# MH-M38_Eagle_circuit.net
KiCad netlist of a schematic drawn in EAGLE
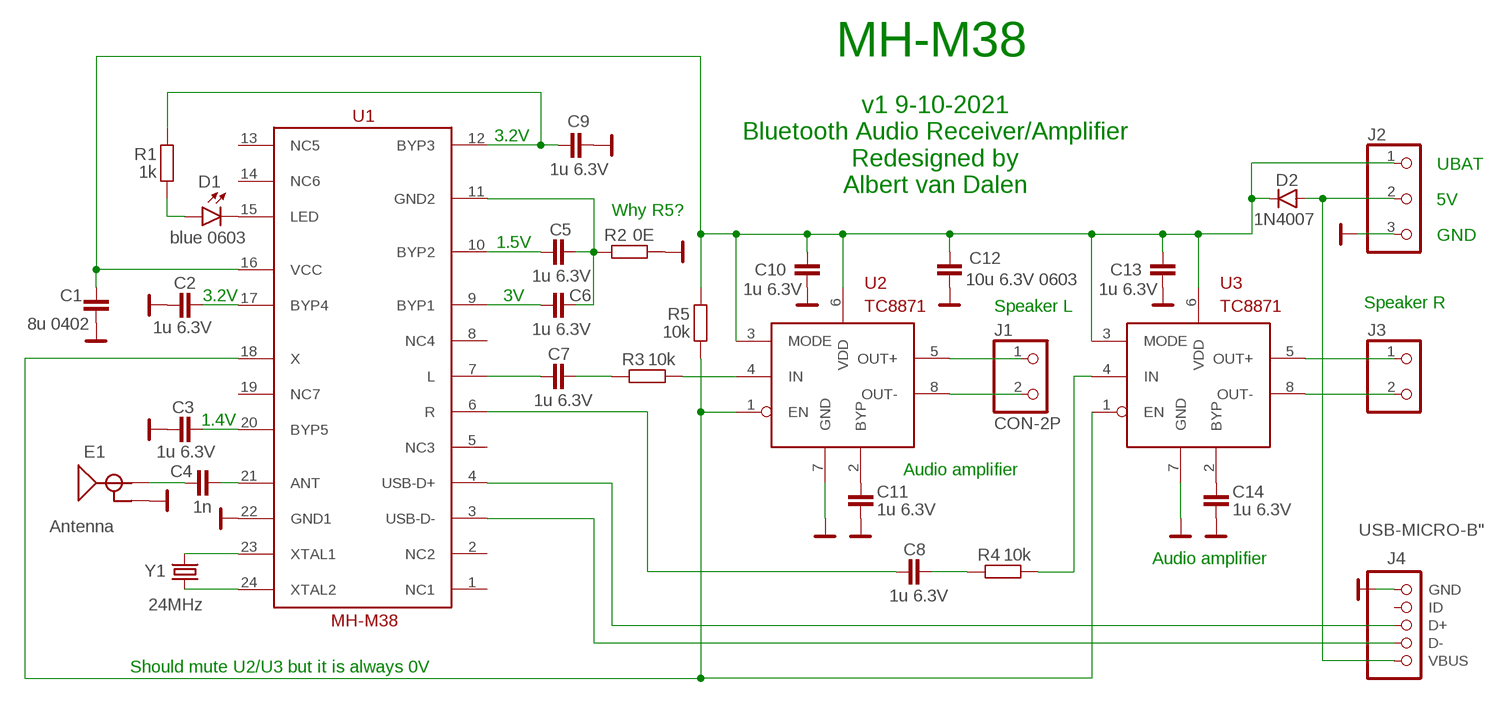
[diagram p0: schematic, sheet 1]

(export (version "E")
  (design (tool "Eeschema 10.0.6"))
  (components
    (comp (ref "C1")
      (value "8u 0402")
      (footprint "eagle-import:0603-SMALL")
      (libsource (lib "eagle-import") (part "SMD-C-0603-SMALL"))
    )
    (comp (ref "C2")
      (value "1u 6.3V")
      (footprint "eagle-import:0402-SMALL")
      (libsource (lib "eagle-import") (part "SMD-C-0402-SMALL"))
    )
    (comp (ref "C3")
      (value "1u 6.3V")
      (footprint "eagle-import:0402-SMALL")
      (libsource (lib "eagle-import") (part "SMD-C-0402-SMALL"))
    )
    (comp (ref "C4")
      (value "1n")
      (footprint "eagle-import:0402-SMALL")
      (libsource (lib "eagle-import") (part "SMD-C-0402-SMALL"))
    )
    (comp (ref "C5")
      (value "1u 6.3V")
      (footprint "eagle-import:0402-SMALL")
      (libsource (lib "eagle-import") (part "SMD-C-0402-SMALL"))
    )
    (comp (ref "C6")
      (value "1u 6.3V")
      (footprint "eagle-import:0402-SMALL")
      (libsource (lib "eagle-import") (part "SMD-C-0402-SMALL"))
    )
    (comp (ref "C7")
      (value "1u 6.3V")
      (footprint "eagle-import:0402-SMALL")
      (libsource (lib "eagle-import") (part "SMD-C-0402-SMALL"))
    )
    (comp (ref "C8")
      (value "1u 6.3V")
      (footprint "eagle-import:0402-SMALL")
      (libsource (lib "eagle-import") (part "SMD-C-0402-SMALL"))
    )
    (comp (ref "C9")
      (value "1u 6.3V")
      (footprint "eagle-import:0402-SMALL")
      (libsource (lib "eagle-import") (part "SMD-C-0402-SMALL"))
    )
    (comp (ref "C10")
      (value "1u 6.3V")
      (footprint "eagle-import:0402-SMALL")
      (libsource (lib "eagle-import") (part "SMD-C-0402-SMALL"))
    )
    (comp (ref "C11")
      (value "1u 6.3V")
      (footprint "eagle-import:0402-SMALL")
      (libsource (lib "eagle-import") (part "SMD-C-0402-SMALL"))
    )
    (comp (ref "C12")
      (value "10u 6.3V 0603")
      (footprint "eagle-import:0603-SMALL")
      (libsource (lib "eagle-import") (part "SMD-C-0603-SMALL"))
    )
    (comp (ref "C13")
      (value "1u 6.3V")
      (footprint "eagle-import:0402-SMALL")
      (libsource (lib "eagle-import") (part "SMD-C-0402-SMALL"))
    )
    (comp (ref "C14")
      (value "1u 6.3V")
      (footprint "eagle-import:0402-SMALL")
      (libsource (lib "eagle-import") (part "SMD-C-0402-SMALL"))
    )
    (comp (ref "D1")
      (value "blue 0603")
      (footprint "eagle-import:LED-0603")
      (libsource (lib "eagle-import") (part "LED"))
    )
    (comp (ref "D2")
      (value "1N4007")
      (footprint "eagle-import:SOD-323")
      (libsource (lib "eagle-import") (part "DIODE-SMD"))
    )
    (comp (ref "E1")
      (value "Antenna")
      (footprint "eagle-import:TRACE_ANTENNA_2.4GHZ_15.2MM")
      (libsource (lib "eagle-import") (part "ANTENNATRACE-15.2MM"))
    )
    (comp (ref "J1")
      (value "CON-2P")
      (footprint "eagle-import:JST-2")
      (libsource (lib "eagle-import") (part "CON-2P"))
    )
    (comp (ref "J2")
      (value "CON-3P")
      (footprint "eagle-import:JST-3")
      (libsource (lib "eagle-import") (part "CON-3P"))
    )
    (comp (ref "J3")
      (value "CON-2P")
      (footprint "eagle-import:JST-2")
      (libsource (lib "eagle-import") (part "CON-2P"))
    )
    (comp (ref "J4")
      (value "USB-MICRO-B\"")
      (footprint "eagle-import:USB-B-MICRO-SMD_V03")
      (libsource (lib "eagle-import") (part "USB-MICRO-B{dblquote}"))
    )
    (comp (ref "R1")
      (value "1k")
      (footprint "eagle-import:0402-SMALL")
      (libsource (lib "eagle-import") (part "SMD-R-0402-SMALL"))
    )
    (comp (ref "R2")
      (value "0E")
      (footprint "eagle-import:0402-SMALL")
      (libsource (lib "eagle-import") (part "SMD-R-0402-SMALL"))
    )
    (comp (ref "R3")
      (value "10k")
      (footprint "eagle-import:0402-SMALL")
      (libsource (lib "eagle-import") (part "SMD-R-0402-SMALL"))
    )
    (comp (ref "R4")
      (value "10k")
      (footprint "eagle-import:0402-SMALL")
      (libsource (lib "eagle-import") (part "SMD-R-0402-SMALL"))
    )
    (comp (ref "R5")
      (value "10k")
      (footprint "eagle-import:0402-SMALL")
      (libsource (lib "eagle-import") (part "SMD-R-0402-SMALL"))
    )
    (comp (ref "U1")
      (value "MH-M38")
      (footprint "eagle-import:TSSOP24-0.65-7.8X4.4MM")
      (libsource (lib "eagle-import") (part "MH-M38"))
    )
    (comp (ref "U2")
      (value "TC8871")
      (footprint "eagle-import:SO08")
      (libsource (lib "eagle-import") (part "TC8871"))
    )
    (comp (ref "U3")
      (value "TC8871")
      (footprint "eagle-import:SO08")
      (libsource (lib "eagle-import") (part "TC8871"))
    )
    (comp (ref "Y1")
      (value "24MHz")
      (footprint "eagle-import:FA-128")
      (libsource (lib "eagle-import") (part "CRYSTAL-SMD128"))
    )
  )
  (nets
    (net (code "1") (name "GND") (class "Default")
      (node (ref "C1") (pin "2") (pinfunction "2_2") (pintype "passive"))
      (node (ref "C10") (pin "2") (pinfunction "2_2") (pintype "passive"))
      (node (ref "C11") (pin "2") (pinfunction "2_2") (pintype "passive"))
      (node (ref "C12") (pin "2") (pinfunction "2_2") (pintype "passive"))
      (node (ref "C13") (pin "2") (pinfunction "2_2") (pintype "passive"))
      (node (ref "C14") (pin "2") (pinfunction "2_2") (pintype "passive"))
      (node (ref "C2") (pin "2") (pinfunction "2_2") (pintype "passive"))
      (node (ref "C3") (pin "2") (pinfunction "2_2") (pintype "passive"))
      (node (ref "C9") (pin "2") (pinfunction "2_2") (pintype "passive"))
      (node (ref "E1") (pin "GND") (pinfunction "GND_GND") (pintype "bidirectional"))
      (node (ref "J2") (pin "3") (pinfunction "3_3") (pintype "passive"))
      (node (ref "J4") (pin "GND") (pinfunction "GND_GND") (pintype "bidirectional"))
      (node (ref "J4") (pin "SHIELD1") (pinfunction "GND_SHIELD1") (pintype "bidirectional"))
      (node (ref "J4") (pin "SHIELD2") (pinfunction "GND_SHIELD2") (pintype "bidirectional"))
      (node (ref "J4") (pin "SHIELD3") (pinfunction "GND_SHIELD3") (pintype "bidirectional"))
      (node (ref "R2") (pin "2") (pinfunction "2_2") (pintype "passive"))
      (node (ref "U1") (pin "22") (pinfunction "GND1_22") (pintype "bidirectional"))
      (node (ref "U2") (pin "7") (pinfunction "GND_7") (pintype "bidirectional"))
      (node (ref "U3") (pin "7") (pinfunction "GND_7") (pintype "bidirectional"))
    )
    (net (code "2") (name "Net-(C7-Pad2)") (class "Default")
      (node (ref "C7") (pin "2") (pinfunction "2_2") (pintype "passive"))
      (node (ref "R3") (pin "1") (pinfunction "1_1") (pintype "passive"))
    )
    (net (code "3") (name "Net-(C8-Pad2)") (class "Default")
      (node (ref "C8") (pin "2") (pinfunction "2_2") (pintype "passive"))
      (node (ref "R4") (pin "1") (pinfunction "1_1") (pintype "passive"))
    )
    (net (code "4") (name "Net-(D1-PadA)") (class "Default")
      (node (ref "D1") (pin "A") (pinfunction "A_A") (pintype "passive"))
      (node (ref "R1") (pin "1") (pinfunction "1_1") (pintype "passive"))
    )
    (net (code "5") (name "Net-(D2-PadA)") (class "Default")
      (node (ref "D2") (pin "A") (pinfunction "A_A") (pintype "passive"))
      (node (ref "J2") (pin "2") (pinfunction "2_2") (pintype "passive"))
      (node (ref "J4") (pin "VBUS") (pinfunction "VBUS_VBUS") (pintype "bidirectional"))
    )
    (net (code "6") (name "Net-(E1-SIGNAL)") (class "Default")
      (node (ref "C4") (pin "2") (pinfunction "2_2") (pintype "passive"))
      (node (ref "E1") (pin "ANT") (pinfunction "SIGNAL_ANT") (pintype "bidirectional"))
    )
    (net (code "7") (name "Net-(U1-ANT)") (class "Default")
      (node (ref "C4") (pin "1") (pinfunction "1_1") (pintype "passive"))
      (node (ref "U1") (pin "21") (pinfunction "ANT_21") (pintype "bidirectional"))
    )
    (net (code "8") (name "Net-(U1-BYP1)") (class "Default")
      (node (ref "C6") (pin "1") (pinfunction "1_1") (pintype "passive"))
      (node (ref "U1") (pin "9") (pinfunction "BYP1_9") (pintype "bidirectional"))
    )
    (net (code "9") (name "Net-(U1-BYP2)") (class "Default")
      (node (ref "C5") (pin "1") (pinfunction "1_1") (pintype "passive"))
      (node (ref "U1") (pin "10") (pinfunction "BYP2_10") (pintype "bidirectional"))
    )
    (net (code "10") (name "Net-(U1-BYP3)") (class "Default")
      (node (ref "C9") (pin "1") (pinfunction "1_1") (pintype "passive"))
      (node (ref "R1") (pin "2") (pinfunction "2_2") (pintype "passive"))
      (node (ref "U1") (pin "12") (pinfunction "BYP3_12") (pintype "bidirectional"))
    )
    (net (code "11") (name "Net-(U1-BYP4)") (class "Default")
      (node (ref "C2") (pin "1") (pinfunction "1_1") (pintype "passive"))
      (node (ref "U1") (pin "17") (pinfunction "BYP4_17") (pintype "bidirectional"))
    )
    (net (code "12") (name "Net-(U1-BYP5)") (class "Default")
      (node (ref "C3") (pin "1") (pinfunction "1_1") (pintype "passive"))
      (node (ref "U1") (pin "20") (pinfunction "BYP5_20") (pintype "bidirectional"))
    )
    (net (code "13") (name "Net-(U1-GND2)") (class "Default")
      (node (ref "C5") (pin "2") (pinfunction "2_2") (pintype "passive"))
      (node (ref "C6") (pin "2") (pinfunction "2_2") (pintype "passive"))
      (node (ref "R2") (pin "1") (pinfunction "1_1") (pintype "passive"))
      (node (ref "U1") (pin "11") (pinfunction "GND2_11") (pintype "bidirectional"))
    )
    (net (code "14") (name "Net-(U1-L)") (class "Default")
      (node (ref "C7") (pin "1") (pinfunction "1_1") (pintype "passive"))
      (node (ref "U1") (pin "7") (pinfunction "L_7") (pintype "bidirectional"))
    )
    (net (code "15") (name "Net-(U1-LED)") (class "Default")
      (node (ref "D1") (pin "C") (pinfunction "C_C") (pintype "passive"))
      (node (ref "U1") (pin "15") (pinfunction "LED_15") (pintype "bidirectional"))
    )
    (net (code "16") (name "Net-(U1-R)") (class "Default")
      (node (ref "C8") (pin "1") (pinfunction "1_1") (pintype "passive"))
      (node (ref "U1") (pin "6") (pinfunction "R_6") (pintype "bidirectional"))
    )
    (net (code "17") (name "Net-(U1-USB-D+)") (class "Default")
      (node (ref "J4") (pin "D+") (pinfunction "D+_D+") (pintype "bidirectional"))
      (node (ref "U1") (pin "4") (pinfunction "USB-D+_4") (pintype "bidirectional"))
    )
    (net (code "18") (name "Net-(U1-USB-D-)") (class "Default")
      (node (ref "J4") (pin "D-") (pinfunction "D-_D-") (pintype "bidirectional"))
      (node (ref "U1") (pin "3") (pinfunction "USB-D-_3") (pintype "bidirectional"))
    )
    (net (code "19") (name "Net-(U1-VCC)") (class "Default")
      (node (ref "C1") (pin "1") (pinfunction "1_1") (pintype "passive"))
      (node (ref "C10") (pin "1") (pinfunction "1_1") (pintype "passive"))
      (node (ref "C12") (pin "1") (pinfunction "1_1") (pintype "passive"))
      (node (ref "C13") (pin "1") (pinfunction "1_1") (pintype "passive"))
      (node (ref "D2") (pin "C") (pinfunction "C_C") (pintype "passive"))
      (node (ref "J2") (pin "1") (pinfunction "1_1") (pintype "passive"))
      (node (ref "R5") (pin "2") (pinfunction "2_2") (pintype "passive"))
      (node (ref "U1") (pin "16") (pinfunction "VCC_16") (pintype "bidirectional"))
      (node (ref "U2") (pin "3") (pinfunction "MODE_3") (pintype "bidirectional"))
      (node (ref "U2") (pin "6") (pinfunction "VDD_6") (pintype "bidirectional"))
      (node (ref "U3") (pin "3") (pinfunction "MODE_3") (pintype "bidirectional"))
      (node (ref "U3") (pin "6") (pinfunction "VDD_6") (pintype "bidirectional"))
    )
    (net (code "20") (name "Net-(U1-X)") (class "Default")
      (node (ref "R5") (pin "1") (pinfunction "1_1") (pintype "passive"))
      (node (ref "U1") (pin "18") (pinfunction "X_18") (pintype "bidirectional"))
      (node (ref "U2") (pin "1") (pinfunction "EN_1") (pintype "bidirectional"))
      (node (ref "U3") (pin "1") (pinfunction "EN_1") (pintype "bidirectional"))
    )
    (net (code "21") (name "Net-(U1-XTAL1)") (class "Default")
      (node (ref "U1") (pin "23") (pinfunction "XTAL1_23") (pintype "bidirectional"))
      (node (ref "Y1") (pin "3") (pinfunction "2_3") (pintype "bidirectional"))
    )
    (net (code "22") (name "Net-(U1-XTAL2)") (class "Default")
      (node (ref "U1") (pin "24") (pinfunction "XTAL2_24") (pintype "bidirectional"))
      (node (ref "Y1") (pin "1") (pinfunction "1_1") (pintype "bidirectional"))
    )
    (net (code "23") (name "Net-(U2-BYP)") (class "Default")
      (node (ref "C11") (pin "1") (pinfunction "1_1") (pintype "passive"))
      (node (ref "U2") (pin "2") (pinfunction "BYP_2") (pintype "bidirectional"))
    )
    (net (code "24") (name "Net-(U2-IN)") (class "Default")
      (node (ref "R3") (pin "2") (pinfunction "2_2") (pintype "passive"))
      (node (ref "U2") (pin "4") (pinfunction "IN_4") (pintype "bidirectional"))
    )
    (net (code "25") (name "Net-(U2-OUT+)") (class "Default")
      (node (ref "J1") (pin "1") (pinfunction "1_1") (pintype "passive"))
      (node (ref "U2") (pin "5") (pinfunction "OUT+_5") (pintype "bidirectional"))
    )
    (net (code "26") (name "Net-(U2-OUT-)") (class "Default")
      (node (ref "J1") (pin "2") (pinfunction "2_2") (pintype "passive"))
      (node (ref "U2") (pin "8") (pinfunction "OUT-_8") (pintype "bidirectional"))
    )
    (net (code "27") (name "Net-(U3-BYP)") (class "Default")
      (node (ref "C14") (pin "1") (pinfunction "1_1") (pintype "passive"))
      (node (ref "U3") (pin "2") (pinfunction "BYP_2") (pintype "bidirectional"))
    )
    (net (code "28") (name "Net-(U3-IN)") (class "Default")
      (node (ref "R4") (pin "2") (pinfunction "2_2") (pintype "passive"))
      (node (ref "U3") (pin "4") (pinfunction "IN_4") (pintype "bidirectional"))
    )
    (net (code "29") (name "Net-(U3-OUT+)") (class "Default")
      (node (ref "J3") (pin "1") (pinfunction "1_1") (pintype "passive"))
      (node (ref "U3") (pin "5") (pinfunction "OUT+_5") (pintype "bidirectional"))
    )
    (net (code "30") (name "Net-(U3-OUT-)") (class "Default")
      (node (ref "J3") (pin "2") (pinfunction "2_2") (pintype "passive"))
      (node (ref "U3") (pin "8") (pinfunction "OUT-_8") (pintype "bidirectional"))
    )
    (net (code "31") (name "unconnected-(J4-PadID)") (class "Default")
      (node (ref "J4") (pin "ID") (pinfunction "ID_ID") (pintype "bidirectional"))
    )
    (net (code "32") (name "unconnected-(U1-NC1-Pad1)") (class "Default")
      (node (ref "U1") (pin "1") (pinfunction "NC1_1") (pintype "bidirectional"))
    )
    (net (code "33") (name "unconnected-(U1-NC2-Pad2)") (class "Default")
      (node (ref "U1") (pin "2") (pinfunction "NC2_2") (pintype "bidirectional"))
    )
    (net (code "34") (name "unconnected-(U1-NC3-Pad5)") (class "Default")
      (node (ref "U1") (pin "5") (pinfunction "NC3_5") (pintype "bidirectional"))
    )
    (net (code "35") (name "unconnected-(U1-NC4-Pad8)") (class "Default")
      (node (ref "U1") (pin "8") (pinfunction "NC4_8") (pintype "bidirectional"))
    )
    (net (code "36") (name "unconnected-(U1-NC5-Pad13)") (class "Default")
      (node (ref "U1") (pin "13") (pinfunction "NC5_13") (pintype "bidirectional"))
    )
    (net (code "37") (name "unconnected-(U1-NC6-Pad14)") (class "Default")
      (node (ref "U1") (pin "14") (pinfunction "NC6_14") (pintype "bidirectional"))
    )
    (net (code "38") (name "unconnected-(U1-NC7-Pad19)") (class "Default")
      (node (ref "U1") (pin "19") (pinfunction "NC7_19") (pintype "bidirectional"))
    )
  )
)
